# Chargers.net
KiCad netlist of a schematic drawn in Altium Designer
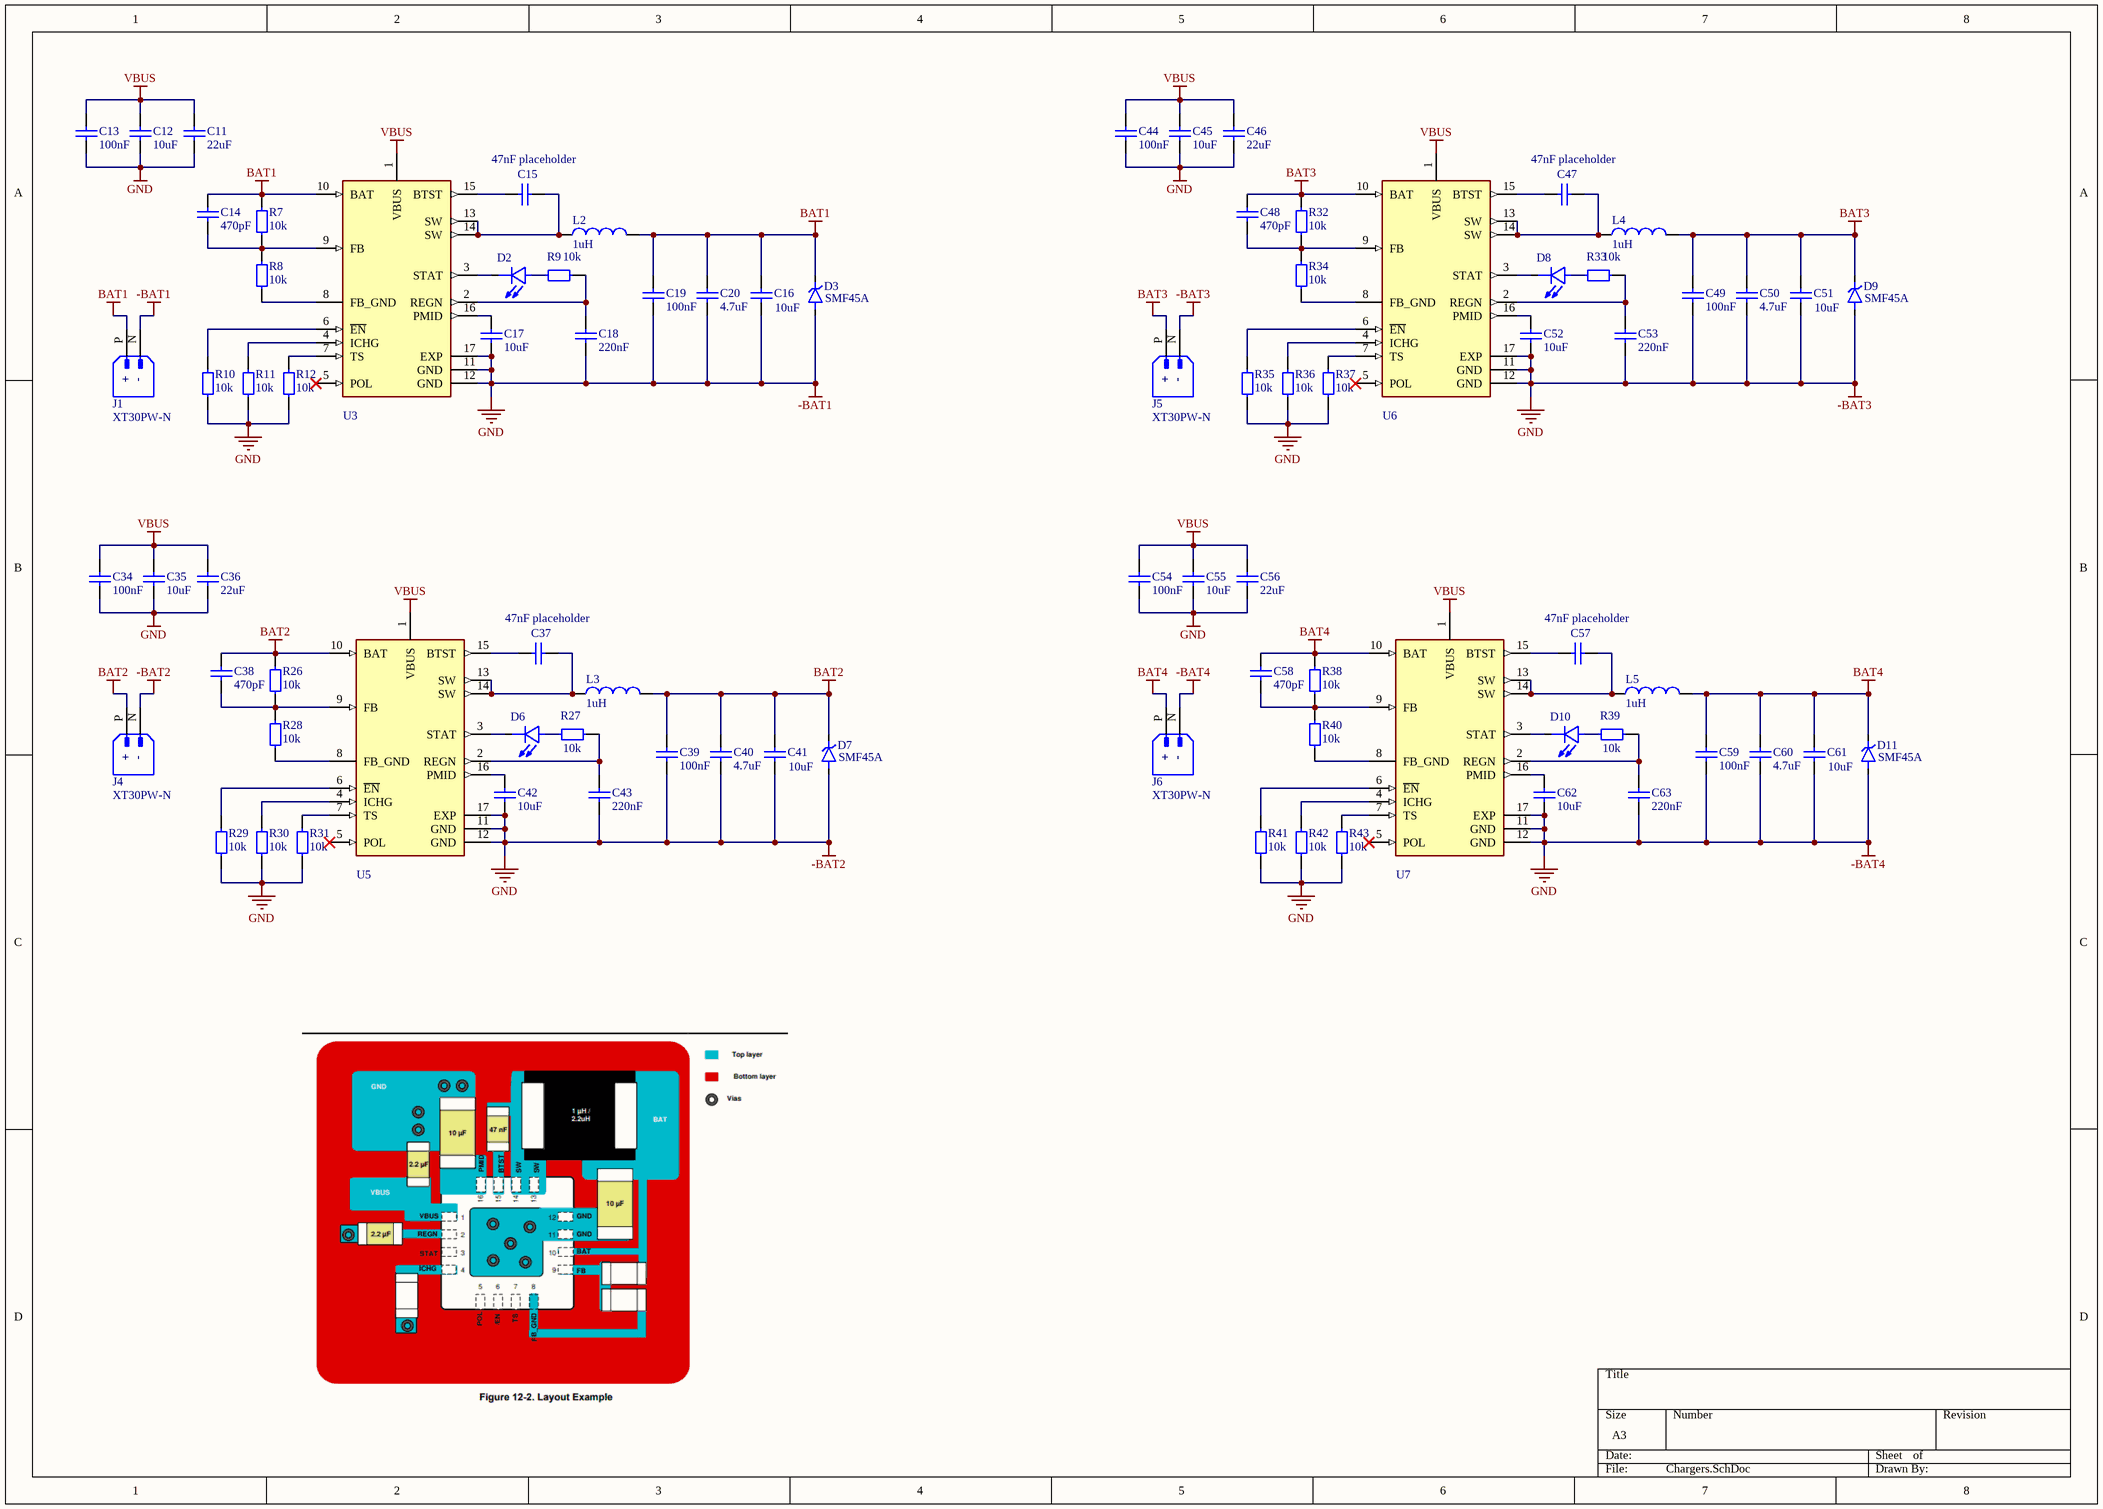
[diagram p0: Chargers.SchDoc]

(export (version "E")
  (design (tool "Eeschema 10.0.6"))
  (components
    (comp (ref "C11")
      (value "22uF")
      (footprint "1210_CAP")
      (description "22uF 50V 1210")
      (libsource (lib "Capacitor") (part "Capacitor 22uF 1210"))
    )
    (comp (ref "C12")
      (value "10uF")
      (footprint "0805_CAP")
      (description "10uF 50V 0805")
      (libsource (lib "Capacitor") (part "Capacitor 10uF 0805"))
    )
    (comp (ref "C13")
      (value "100nF")
      (footprint "0603 Capacitor")
      (description "100nF 50V 0603")
      (libsource (lib "Capacitor") (part "Capacitor 100nF 0603"))
    )
    (comp (ref "C14")
      (value "470pF")
      (footprint "0603 Capacitor")
      (description "470pF 50V 0603")
      (libsource (lib "Capacitor") (part "Capacitor 470pF 0603"))
    )
    (comp (ref "C15")
      (value "47nF placeholder")
      (footprint "0603 Capacitor")
      (description "1nF 50V 0603")
      (libsource (lib "Capacitor") (part "Capacitor 1nF 0603"))
    )
    (comp (ref "C16")
      (value "10uF")
      (footprint "0805_CAP")
      (description "10uF 50V 0805")
      (libsource (lib "Capacitor") (part "Capacitor 10uF 0805"))
    )
    (comp (ref "C17")
      (value "10uF")
      (footprint "0805_CAP")
      (description "10uF 50V 0805")
      (libsource (lib "Capacitor") (part "Capacitor 10uF 0805"))
    )
    (comp (ref "C18")
      (value "220nF")
      (footprint "0603 Capacitor")
      (description "220nF 50V 0603")
      (libsource (lib "Capacitor") (part "Capacitor 220nF 0603"))
    )
    (comp (ref "C19")
      (value "100nF")
      (footprint "0603 Capacitor")
      (description "100nF 50V 0603")
      (libsource (lib "Capacitor") (part "Capacitor 100nF 0603"))
    )
    (comp (ref "C20")
      (value "4.7uF")
      (footprint "0805_CAP")
      (description "4.7uF 50V 0805")
      (libsource (lib "Capacitor") (part "Capacitor 4.7uF 0805"))
    )
    (comp (ref "C34")
      (value "100nF")
      (footprint "0603 Capacitor")
      (description "100nF 50V 0603")
      (libsource (lib "Capacitor") (part "Capacitor 100nF 0603"))
    )
    (comp (ref "C35")
      (value "10uF")
      (footprint "0805_CAP")
      (description "10uF 50V 0805")
      (libsource (lib "Capacitor") (part "Capacitor 10uF 0805"))
    )
    (comp (ref "C36")
      (value "22uF")
      (footprint "1210_CAP")
      (description "22uF 50V 1210")
      (libsource (lib "Capacitor") (part "Capacitor 22uF 1210"))
    )
    (comp (ref "C37")
      (value "47nF placeholder")
      (footprint "0603 Capacitor")
      (description "1nF 50V 0603")
      (libsource (lib "Capacitor") (part "Capacitor 1nF 0603"))
    )
    (comp (ref "C38")
      (value "470pF")
      (footprint "0603 Capacitor")
      (description "470pF 50V 0603")
      (libsource (lib "Capacitor") (part "Capacitor 470pF 0603"))
    )
    (comp (ref "C39")
      (value "100nF")
      (footprint "0603 Capacitor")
      (description "100nF 50V 0603")
      (libsource (lib "Capacitor") (part "Capacitor 100nF 0603"))
    )
    (comp (ref "C40")
      (value "4.7uF")
      (footprint "0805_CAP")
      (description "4.7uF 50V 0805")
      (libsource (lib "Capacitor") (part "Capacitor 4.7uF 0805"))
    )
    (comp (ref "C41")
      (value "10uF")
      (footprint "0805_CAP")
      (description "10uF 50V 0805")
      (libsource (lib "Capacitor") (part "Capacitor 10uF 0805"))
    )
    (comp (ref "C42")
      (value "10uF")
      (footprint "0805_CAP")
      (description "10uF 50V 0805")
      (libsource (lib "Capacitor") (part "Capacitor 10uF 0805"))
    )
    (comp (ref "C43")
      (value "220nF")
      (footprint "0603 Capacitor")
      (description "220nF 50V 0603")
      (libsource (lib "Capacitor") (part "Capacitor 220nF 0603"))
    )
    (comp (ref "C44")
      (value "100nF")
      (footprint "0603 Capacitor")
      (description "100nF 50V 0603")
      (libsource (lib "Capacitor") (part "Capacitor 100nF 0603"))
    )
    (comp (ref "C45")
      (value "10uF")
      (footprint "0805_CAP")
      (description "10uF 50V 0805")
      (libsource (lib "Capacitor") (part "Capacitor 10uF 0805"))
    )
    (comp (ref "C46")
      (value "22uF")
      (footprint "1210_CAP")
      (description "22uF 50V 1210")
      (libsource (lib "Capacitor") (part "Capacitor 22uF 1210"))
    )
    (comp (ref "C47")
      (value "47nF placeholder")
      (footprint "0603 Capacitor")
      (description "1nF 50V 0603")
      (libsource (lib "Capacitor") (part "Capacitor 1nF 0603"))
    )
    (comp (ref "C48")
      (value "470pF")
      (footprint "0603 Capacitor")
      (description "470pF 50V 0603")
      (libsource (lib "Capacitor") (part "Capacitor 470pF 0603"))
    )
    (comp (ref "C49")
      (value "100nF")
      (footprint "0603 Capacitor")
      (description "100nF 50V 0603")
      (libsource (lib "Capacitor") (part "Capacitor 100nF 0603"))
    )
    (comp (ref "C50")
      (value "4.7uF")
      (footprint "0805_CAP")
      (description "4.7uF 50V 0805")
      (libsource (lib "Capacitor") (part "Capacitor 4.7uF 0805"))
    )
    (comp (ref "C51")
      (value "10uF")
      (footprint "0805_CAP")
      (description "10uF 50V 0805")
      (libsource (lib "Capacitor") (part "Capacitor 10uF 0805"))
    )
    (comp (ref "C52")
      (value "10uF")
      (footprint "0805_CAP")
      (description "10uF 50V 0805")
      (libsource (lib "Capacitor") (part "Capacitor 10uF 0805"))
    )
    (comp (ref "C53")
      (value "220nF")
      (footprint "0603 Capacitor")
      (description "220nF 50V 0603")
      (libsource (lib "Capacitor") (part "Capacitor 220nF 0603"))
    )
    (comp (ref "C54")
      (value "100nF")
      (footprint "0603 Capacitor")
      (description "100nF 50V 0603")
      (libsource (lib "Capacitor") (part "Capacitor 100nF 0603"))
    )
    (comp (ref "C55")
      (value "10uF")
      (footprint "0805_CAP")
      (description "10uF 50V 0805")
      (libsource (lib "Capacitor") (part "Capacitor 10uF 0805"))
    )
    (comp (ref "C56")
      (value "22uF")
      (footprint "1210_CAP")
      (description "22uF 50V 1210")
      (libsource (lib "Capacitor") (part "Capacitor 22uF 1210"))
    )
    (comp (ref "C57")
      (value "47nF placeholder")
      (footprint "0603 Capacitor")
      (description "1nF 50V 0603")
      (libsource (lib "Capacitor") (part "Capacitor 1nF 0603"))
    )
    (comp (ref "C58")
      (value "470pF")
      (footprint "0603 Capacitor")
      (description "470pF 50V 0603")
      (libsource (lib "Capacitor") (part "Capacitor 470pF 0603"))
    )
    (comp (ref "C59")
      (value "100nF")
      (footprint "0603 Capacitor")
      (description "100nF 50V 0603")
      (libsource (lib "Capacitor") (part "Capacitor 100nF 0603"))
    )
    (comp (ref "C60")
      (value "4.7uF")
      (footprint "0805_CAP")
      (description "4.7uF 50V 0805")
      (libsource (lib "Capacitor") (part "Capacitor 4.7uF 0805"))
    )
    (comp (ref "C61")
      (value "10uF")
      (footprint "0805_CAP")
      (description "10uF 50V 0805")
      (libsource (lib "Capacitor") (part "Capacitor 10uF 0805"))
    )
    (comp (ref "C62")
      (value "10uF")
      (footprint "0805_CAP")
      (description "10uF 50V 0805")
      (libsource (lib "Capacitor") (part "Capacitor 10uF 0805"))
    )
    (comp (ref "C63")
      (value "220nF")
      (footprint "0603 Capacitor")
      (description "220nF 50V 0603")
      (libsource (lib "Capacitor") (part "Capacitor 220nF 0603"))
    )
    (comp (ref "D2")
      (value "LTST-C190KGKT")
      (footprint "LED 0603")
      (description "1.6x0.8mm Smd Chip Led Lamp")
      (fields (field (name "MF") "Kingbright") (field (name "MP") "KPT-1608ZGC"))
      (libsource (lib "LED") (part "LED 0603"))
    )
    (comp (ref "D3")
      (value "SMF45A")
      (footprint "SOD3718X102N")
      (description "1-channel  50V ultra-low-capacitance IEC ESD protection diode")
      (fields (field (name "MF") "Texas Instruments") (field (name "MP") "TPD1E05U06DPYR"))
      (libsource (lib "TVS") (part "SMF45A"))
    )
    (comp (ref "D6")
      (value "LTST-C190KGKT")
      (footprint "LED 0603")
      (description "1.6x0.8mm Smd Chip Led Lamp")
      (fields (field (name "MF") "Kingbright") (field (name "MP") "KPT-1608ZGC"))
      (libsource (lib "LED") (part "LED 0603"))
    )
    (comp (ref "D7")
      (value "SMF45A")
      (footprint "SOD3718X102N")
      (description "1-channel  50V ultra-low-capacitance IEC ESD protection diode")
      (fields (field (name "MF") "Texas Instruments") (field (name "MP") "TPD1E05U06DPYR"))
      (libsource (lib "TVS") (part "SMF45A"))
    )
    (comp (ref "D8")
      (value "LTST-C190KGKT")
      (footprint "LED 0603")
      (description "1.6x0.8mm Smd Chip Led Lamp")
      (fields (field (name "MF") "Kingbright") (field (name "MP") "KPT-1608ZGC"))
      (libsource (lib "LED") (part "LED 0603"))
    )
    (comp (ref "D9")
      (value "SMF45A")
      (footprint "SOD3718X102N")
      (description "1-channel  50V ultra-low-capacitance IEC ESD protection diode")
      (fields (field (name "MF") "Texas Instruments") (field (name "MP") "TPD1E05U06DPYR"))
      (libsource (lib "TVS") (part "SMF45A"))
    )
    (comp (ref "D10")
      (value "LTST-C190KGKT")
      (footprint "LED 0603")
      (description "1.6x0.8mm Smd Chip Led Lamp")
      (fields (field (name "MF") "Kingbright") (field (name "MP") "KPT-1608ZGC"))
      (libsource (lib "LED") (part "LED 0603"))
    )
    (comp (ref "D11")
      (value "SMF45A")
      (footprint "SOD3718X102N")
      (description "1-channel  50V ultra-low-capacitance IEC ESD protection diode")
      (fields (field (name "MF") "Texas Instruments") (field (name "MP") "TPD1E05U06DPYR"))
      (libsource (lib "TVS") (part "SMF45A"))
    )
    (comp (ref "J1")
      (value "XT30PW-N")
      (footprint "AMASS_XT30UPB-M")
      (description "Socket; DC supply; XT30; male; PIN: 2; on PCBs; THT; straight, Colour: yellow")
      (fields (field (name "MF") "AMASS") (field (name "MP") "XT30PW-M"))
      (libsource (lib "Connector") (part "XT30PW-N"))
    )
    (comp (ref "J4")
      (value "XT30PW-N")
      (footprint "AMASS_XT30UPB-M")
      (description "Socket; DC supply; XT30; male; PIN: 2; on PCBs; THT; straight, Colour: yellow")
      (fields (field (name "MF") "AMASS") (field (name "MP") "XT30PW-M"))
      (libsource (lib "Connector") (part "XT30PW-N"))
    )
    (comp (ref "J5")
      (value "XT30PW-N")
      (footprint "AMASS_XT30UPB-M")
      (description "Socket; DC supply; XT30; male; PIN: 2; on PCBs; THT; straight, Colour: yellow")
      (fields (field (name "MF") "AMASS") (field (name "MP") "XT30PW-M"))
      (libsource (lib "Connector") (part "XT30PW-N"))
    )
    (comp (ref "J6")
      (value "XT30PW-N")
      (footprint "AMASS_XT30UPB-M")
      (description "Socket; DC supply; XT30; male; PIN: 2; on PCBs; THT; straight, Colour: yellow")
      (fields (field (name "MF") "AMASS") (field (name "MP") "XT30PW-M"))
      (libsource (lib "Connector") (part "XT30PW-N"))
    )
    (comp (ref "L2")
      (value "1uH")
      (footprint "HPPC05030")
      (description "1uH 9A  8.9mΩ")
      (fields (field (name "Comment") "HPPC05030-1R0M-Q8"))
      (libsource (lib "Inductor") (part "1uH 9A"))
    )
    (comp (ref "L3")
      (value "1uH")
      (footprint "HPPC05030")
      (description "1uH 9A  8.9mΩ")
      (fields (field (name "Comment") "HPPC05030-1R0M-Q8"))
      (libsource (lib "Inductor") (part "1uH 9A"))
    )
    (comp (ref "L4")
      (value "1uH")
      (footprint "HPPC05030")
      (description "1uH 9A  8.9mΩ")
      (fields (field (name "Comment") "HPPC05030-1R0M-Q8"))
      (libsource (lib "Inductor") (part "1uH 9A"))
    )
    (comp (ref "L5")
      (value "1uH")
      (footprint "HPPC05030")
      (description "1uH 9A  8.9mΩ")
      (fields (field (name "Comment") "HPPC05030-1R0M-Q8"))
      (libsource (lib "Inductor") (part "1uH 9A"))
    )
    (comp (ref "R7")
      (value "10k")
      (footprint "0603 Resistor")
      (description "10k 0603")
      (libsource (lib "Resistors") (part "Resistor 10k 0603"))
    )
    (comp (ref "R8")
      (value "10k")
      (footprint "0603 Resistor")
      (description "10k 0603")
      (libsource (lib "Resistors") (part "Resistor 10k 0603"))
    )
    (comp (ref "R9")
      (value "10k")
      (footprint "0603 Resistor")
      (description "10k 0603")
      (libsource (lib "Resistors") (part "Resistor 10k 0603"))
    )
    (comp (ref "R10")
      (value "10k")
      (footprint "0603 Resistor")
      (description "10k 0603")
      (libsource (lib "Resistors") (part "Resistor 10k 0603"))
    )
    (comp (ref "R11")
      (value "10k")
      (footprint "0603 Resistor")
      (description "10k 0603")
      (libsource (lib "Resistors") (part "Resistor 10k 0603"))
    )
    (comp (ref "R12")
      (value "10k")
      (footprint "0603 Resistor")
      (description "10k 0603")
      (libsource (lib "Resistors") (part "Resistor 10k 0603"))
    )
    (comp (ref "R26")
      (value "10k")
      (footprint "0603 Resistor")
      (description "10k 0603")
      (libsource (lib "Resistors") (part "Resistor 10k 0603"))
    )
    (comp (ref "R27")
      (value "10k")
      (footprint "0603 Resistor")
      (description "10k 0603")
      (libsource (lib "Resistors") (part "Resistor 10k 0603"))
    )
    (comp (ref "R28")
      (value "10k")
      (footprint "0603 Resistor")
      (description "10k 0603")
      (libsource (lib "Resistors") (part "Resistor 10k 0603"))
    )
    (comp (ref "R29")
      (value "10k")
      (footprint "0603 Resistor")
      (description "10k 0603")
      (libsource (lib "Resistors") (part "Resistor 10k 0603"))
    )
    (comp (ref "R30")
      (value "10k")
      (footprint "0603 Resistor")
      (description "10k 0603")
      (libsource (lib "Resistors") (part "Resistor 10k 0603"))
    )
    (comp (ref "R31")
      (value "10k")
      (footprint "0603 Resistor")
      (description "10k 0603")
      (libsource (lib "Resistors") (part "Resistor 10k 0603"))
    )
    (comp (ref "R32")
      (value "10k")
      (footprint "0603 Resistor")
      (description "10k 0603")
      (libsource (lib "Resistors") (part "Resistor 10k 0603"))
    )
    (comp (ref "R33")
      (value "10k")
      (footprint "0603 Resistor")
      (description "10k 0603")
      (libsource (lib "Resistors") (part "Resistor 10k 0603"))
    )
    (comp (ref "R34")
      (value "10k")
      (footprint "0603 Resistor")
      (description "10k 0603")
      (libsource (lib "Resistors") (part "Resistor 10k 0603"))
    )
    (comp (ref "R35")
      (value "10k")
      (footprint "0603 Resistor")
      (description "10k 0603")
      (libsource (lib "Resistors") (part "Resistor 10k 0603"))
    )
    (comp (ref "R36")
      (value "10k")
      (footprint "0603 Resistor")
      (description "10k 0603")
      (libsource (lib "Resistors") (part "Resistor 10k 0603"))
    )
    (comp (ref "R37")
      (value "10k")
      (footprint "0603 Resistor")
      (description "10k 0603")
      (libsource (lib "Resistors") (part "Resistor 10k 0603"))
    )
    (comp (ref "R38")
      (value "10k")
      (footprint "0603 Resistor")
      (description "10k 0603")
      (libsource (lib "Resistors") (part "Resistor 10k 0603"))
    )
    (comp (ref "R39")
      (value "10k")
      (footprint "0603 Resistor")
      (description "10k 0603")
      (libsource (lib "Resistors") (part "Resistor 10k 0603"))
    )
    (comp (ref "R40")
      (value "10k")
      (footprint "0603 Resistor")
      (description "10k 0603")
      (libsource (lib "Resistors") (part "Resistor 10k 0603"))
    )
    (comp (ref "R41")
      (value "10k")
      (footprint "0603 Resistor")
      (description "10k 0603")
      (libsource (lib "Resistors") (part "Resistor 10k 0603"))
    )
    (comp (ref "R42")
      (value "10k")
      (footprint "0603 Resistor")
      (description "10k 0603")
      (libsource (lib "Resistors") (part "Resistor 10k 0603"))
    )
    (comp (ref "R43")
      (value "10k")
      (footprint "0603 Resistor")
      (description "10k 0603")
      (libsource (lib "Resistors") (part "Resistor 10k 0603"))
    )
    (comp (ref "U3")
      (value "BQ25306RTER")
      (footprint "IC_BQ25306RTER")
      (description "TI Standalone 17-V, 3A 1-2 cell buck battery charger")
      (fields (field (name "MF") "Texas Instruments"))
      (libsource (lib "IC") (part "BQ25306RTER"))
    )
    (comp (ref "U5")
      (value "BQ25306RTER")
      (footprint "IC_BQ25306RTER")
      (description "TI Standalone 17-V, 3A 1-2 cell buck battery charger")
      (fields (field (name "MF") "Texas Instruments"))
      (libsource (lib "IC") (part "BQ25306RTER"))
    )
    (comp (ref "U6")
      (value "BQ25306RTER")
      (footprint "IC_BQ25306RTER")
      (description "TI Standalone 17-V, 3A 1-2 cell buck battery charger")
      (fields (field (name "MF") "Texas Instruments"))
      (libsource (lib "IC") (part "BQ25306RTER"))
    )
    (comp (ref "U7")
      (value "BQ25306RTER")
      (footprint "IC_BQ25306RTER")
      (description "TI Standalone 17-V, 3A 1-2 cell buck battery charger")
      (fields (field (name "MF") "Texas Instruments"))
      (libsource (lib "IC") (part "BQ25306RTER"))
    )
  )
  (nets
    (net (code "1") (name "-BAT1") (class "Default")
      (node (ref "C11") (pin "2") (pinfunction "2_2") (pintype "passive"))
      (node (ref "C12") (pin "2") (pinfunction "2_2") (pintype "passive"))
      (node (ref "C13") (pin "2") (pinfunction "2_2") (pintype "passive"))
      (node (ref "C16") (pin "1") (pinfunction "1_1") (pintype "passive"))
      (node (ref "C17") (pin "1") (pinfunction "1_1") (pintype "passive"))
      (node (ref "C18") (pin "1") (pinfunction "1_1") (pintype "passive"))
      (node (ref "C19") (pin "1") (pinfunction "1_1") (pintype "passive"))
      (node (ref "C20") (pin "1") (pinfunction "1_1") (pintype "passive"))
      (node (ref "C34") (pin "2") (pinfunction "2_2") (pintype "passive"))
      (node (ref "C35") (pin "2") (pinfunction "2_2") (pintype "passive"))
      (node (ref "C36") (pin "2") (pinfunction "2_2") (pintype "passive"))
      (node (ref "C39") (pin "1") (pinfunction "1_1") (pintype "passive"))
      (node (ref "C40") (pin "1") (pinfunction "1_1") (pintype "passive"))
      (node (ref "C41") (pin "1") (pinfunction "1_1") (pintype "passive"))
      (node (ref "C42") (pin "1") (pinfunction "1_1") (pintype "passive"))
      (node (ref "C43") (pin "1") (pinfunction "1_1") (pintype "passive"))
      (node (ref "C44") (pin "2") (pinfunction "2_2") (pintype "passive"))
      (node (ref "C45") (pin "2") (pinfunction "2_2") (pintype "passive"))
      (node (ref "C46") (pin "2") (pinfunction "2_2") (pintype "passive"))
      (node (ref "C49") (pin "1") (pinfunction "1_1") (pintype "passive"))
      (node (ref "C50") (pin "1") (pinfunction "1_1") (pintype "passive"))
      (node (ref "C51") (pin "1") (pinfunction "1_1") (pintype "passive"))
      (node (ref "C52") (pin "1") (pinfunction "1_1") (pintype "passive"))
      (node (ref "C53") (pin "1") (pinfunction "1_1") (pintype "passive"))
      (node (ref "C54") (pin "2") (pinfunction "2_2") (pintype "passive"))
      (node (ref "C55") (pin "2") (pinfunction "2_2") (pintype "passive"))
      (node (ref "C56") (pin "2") (pinfunction "2_2") (pintype "passive"))
      (node (ref "C59") (pin "1") (pinfunction "1_1") (pintype "passive"))
      (node (ref "C60") (pin "1") (pinfunction "1_1") (pintype "passive"))
      (node (ref "C61") (pin "1") (pinfunction "1_1") (pintype "passive"))
      (node (ref "C62") (pin "1") (pinfunction "1_1") (pintype "passive"))
      (node (ref "C63") (pin "1") (pinfunction "1_1") (pintype "passive"))
      (node (ref "D11") (pin "A") (pinfunction "2_A") (pintype "passive"))
      (node (ref "D3") (pin "A") (pinfunction "2_A") (pintype "passive"))
      (node (ref "D7") (pin "A") (pinfunction "2_A") (pintype "passive"))
      (node (ref "D9") (pin "A") (pinfunction "2_A") (pintype "passive"))
      (node (ref "J1") (pin "N") (pinfunction "N_N") (pintype "power_in"))
      (node (ref "J4") (pin "N") (pinfunction "N_N") (pintype "power_in"))
      (node (ref "J5") (pin "N") (pinfunction "N_N") (pintype "power_in"))
      (node (ref "J6") (pin "N") (pinfunction "N_N") (pintype "power_in"))
      (node (ref "R10") (pin "1") (pinfunction "CCW_1") (pintype "passive"))
      (node (ref "R11") (pin "1") (pinfunction "CCW_1") (pintype "passive"))
      (node (ref "R12") (pin "1") (pinfunction "CCW_1") (pintype "passive"))
      (node (ref "R29") (pin "1") (pinfunction "CCW_1") (pintype "passive"))
      (node (ref "R30") (pin "1") (pinfunction "CCW_1") (pintype "passive"))
      (node (ref "R31") (pin "1") (pinfunction "CCW_1") (pintype "passive"))
      (node (ref "R35") (pin "1") (pinfunction "CCW_1") (pintype "passive"))
      (node (ref "R36") (pin "1") (pinfunction "CCW_1") (pintype "passive"))
      (node (ref "R37") (pin "1") (pinfunction "CCW_1") (pintype "passive"))
      (node (ref "R41") (pin "1") (pinfunction "CCW_1") (pintype "passive"))
      (node (ref "R42") (pin "1") (pinfunction "CCW_1") (pintype "passive"))
      (node (ref "R43") (pin "1") (pinfunction "CCW_1") (pintype "passive"))
      (node (ref "U3") (pin "11") (pinfunction "GND_11") (pintype "power_in"))
      (node (ref "U3") (pin "12") (pinfunction "GND_12") (pintype "power_in"))
      (node (ref "U3") (pin "17") (pinfunction "EXP_17") (pintype "power_in"))
      (node (ref "U5") (pin "11") (pinfunction "GND_11") (pintype "power_in"))
      (node (ref "U5") (pin "12") (pinfunction "GND_12") (pintype "power_in"))
      (node (ref "U5") (pin "17") (pinfunction "EXP_17") (pintype "power_in"))
      (node (ref "U6") (pin "11") (pinfunction "GND_11") (pintype "power_in"))
      (node (ref "U6") (pin "12") (pinfunction "GND_12") (pintype "power_in"))
      (node (ref "U6") (pin "17") (pinfunction "EXP_17") (pintype "power_in"))
      (node (ref "U7") (pin "11") (pinfunction "GND_11") (pintype "power_in"))
      (node (ref "U7") (pin "12") (pinfunction "GND_12") (pintype "power_in"))
      (node (ref "U7") (pin "17") (pinfunction "EXP_17") (pintype "power_in"))
    )
    (net (code "2") (name "BAT1") (class "Default")
      (node (ref "C14") (pin "2") (pinfunction "2_2") (pintype "passive"))
      (node (ref "C16") (pin "2") (pinfunction "2_2") (pintype "passive"))
      (node (ref "C19") (pin "2") (pinfunction "2_2") (pintype "passive"))
      (node (ref "C20") (pin "2") (pinfunction "2_2") (pintype "passive"))
      (node (ref "D3") (pin "C") (pinfunction "K1_C") (pintype "passive"))
      (node (ref "J1") (pin "P") (pinfunction "+_P") (pintype "power_in"))
      (node (ref "L2") (pin "2") (pinfunction "2_2") (pintype "passive"))
      (node (ref "R7") (pin "2") (pinfunction "CW_2") (pintype "passive"))
      (node (ref "U3") (pin "10") (pinfunction "BAT_10") (pintype "input"))
    )
    (net (code "3") (name "BAT2") (class "Default")
      (node (ref "C38") (pin "2") (pinfunction "2_2") (pintype "passive"))
      (node (ref "C39") (pin "2") (pinfunction "2_2") (pintype "passive"))
      (node (ref "C40") (pin "2") (pinfunction "2_2") (pintype "passive"))
      (node (ref "C41") (pin "2") (pinfunction "2_2") (pintype "passive"))
      (node (ref "D7") (pin "C") (pinfunction "K1_C") (pintype "passive"))
      (node (ref "J4") (pin "P") (pinfunction "+_P") (pintype "power_in"))
      (node (ref "L3") (pin "2") (pinfunction "2_2") (pintype "passive"))
      (node (ref "R26") (pin "2") (pinfunction "CW_2") (pintype "passive"))
      (node (ref "U5") (pin "10") (pinfunction "BAT_10") (pintype "input"))
    )
    (net (code "4") (name "BAT3") (class "Default")
      (node (ref "C48") (pin "2") (pinfunction "2_2") (pintype "passive"))
      (node (ref "C49") (pin "2") (pinfunction "2_2") (pintype "passive"))
      (node (ref "C50") (pin "2") (pinfunction "2_2") (pintype "passive"))
      (node (ref "C51") (pin "2") (pinfunction "2_2") (pintype "passive"))
      (node (ref "D9") (pin "C") (pinfunction "K1_C") (pintype "passive"))
      (node (ref "J5") (pin "P") (pinfunction "+_P") (pintype "power_in"))
      (node (ref "L4") (pin "2") (pinfunction "2_2") (pintype "passive"))
      (node (ref "R32") (pin "2") (pinfunction "CW_2") (pintype "passive"))
      (node (ref "U6") (pin "10") (pinfunction "BAT_10") (pintype "input"))
    )
    (net (code "5") (name "BAT4") (class "Default")
      (node (ref "C58") (pin "2") (pinfunction "2_2") (pintype "passive"))
      (node (ref "C59") (pin "2") (pinfunction "2_2") (pintype "passive"))
      (node (ref "C60") (pin "2") (pinfunction "2_2") (pintype "passive"))
      (node (ref "C61") (pin "2") (pinfunction "2_2") (pintype "passive"))
      (node (ref "D11") (pin "C") (pinfunction "K1_C") (pintype "passive"))
      (node (ref "J6") (pin "P") (pinfunction "+_P") (pintype "power_in"))
      (node (ref "L5") (pin "2") (pinfunction "2_2") (pintype "passive"))
      (node (ref "R38") (pin "2") (pinfunction "CW_2") (pintype "passive"))
      (node (ref "U7") (pin "10") (pinfunction "BAT_10") (pintype "input"))
    )
    (net (code "6") (name "Net-(C15-Pad1)") (class "Default")
      (node (ref "C15") (pin "1") (pinfunction "1_1") (pintype "passive"))
      (node (ref "L2") (pin "1") (pinfunction "1_1") (pintype "passive"))
      (node (ref "U3") (pin "13") (pinfunction "SW_13") (pintype "output"))
      (node (ref "U3") (pin "14") (pinfunction "SW_14") (pintype "output"))
    )
    (net (code "7") (name "Net-(C37-Pad1)") (class "Default")
      (node (ref "C37") (pin "1") (pinfunction "1_1") (pintype "passive"))
      (node (ref "L3") (pin "1") (pinfunction "1_1") (pintype "passive"))
      (node (ref "U5") (pin "13") (pinfunction "SW_13") (pintype "output"))
      (node (ref "U5") (pin "14") (pinfunction "SW_14") (pintype "output"))
    )
    (net (code "8") (name "Net-(C47-Pad1)") (class "Default")
      (node (ref "C47") (pin "1") (pinfunction "1_1") (pintype "passive"))
      (node (ref "L4") (pin "1") (pinfunction "1_1") (pintype "passive"))
      (node (ref "U6") (pin "13") (pinfunction "SW_13") (pintype "output"))
      (node (ref "U6") (pin "14") (pinfunction "SW_14") (pintype "output"))
    )
    (net (code "9") (name "Net-(C57-Pad1)") (class "Default")
      (node (ref "C57") (pin "1") (pinfunction "1_1") (pintype "passive"))
      (node (ref "L5") (pin "1") (pinfunction "1_1") (pintype "passive"))
      (node (ref "U7") (pin "13") (pinfunction "SW_13") (pintype "output"))
      (node (ref "U7") (pin "14") (pinfunction "SW_14") (pintype "output"))
    )
    (net (code "10") (name "Net-(D2-A)") (class "Default")
      (node (ref "D2") (pin "1") (pinfunction "A_1") (pintype "passive"))
      (node (ref "R9") (pin "2") (pinfunction "CW_2") (pintype "passive"))
    )
    (net (code "11") (name "Net-(D2-C)") (class "Default")
      (node (ref "D2") (pin "2") (pinfunction "C_2") (pintype "passive"))
      (node (ref "U3") (pin "3") (pinfunction "STAT_3") (pintype "output"))
    )
    (net (code "12") (name "Net-(D6-A)") (class "Default")
      (node (ref "D6") (pin "1") (pinfunction "A_1") (pintype "passive"))
      (node (ref "R27") (pin "2") (pinfunction "CW_2") (pintype "passive"))
    )
    (net (code "13") (name "Net-(D6-C)") (class "Default")
      (node (ref "D6") (pin "2") (pinfunction "C_2") (pintype "passive"))
      (node (ref "U5") (pin "3") (pinfunction "STAT_3") (pintype "output"))
    )
    (net (code "14") (name "Net-(D8-A)") (class "Default")
      (node (ref "D8") (pin "1") (pinfunction "A_1") (pintype "passive"))
      (node (ref "R33") (pin "2") (pinfunction "CW_2") (pintype "passive"))
    )
    (net (code "15") (name "Net-(D8-C)") (class "Default")
      (node (ref "D8") (pin "2") (pinfunction "C_2") (pintype "passive"))
      (node (ref "U6") (pin "3") (pinfunction "STAT_3") (pintype "output"))
    )
    (net (code "16") (name "Net-(D10-A)") (class "Default")
      (node (ref "D10") (pin "1") (pinfunction "A_1") (pintype "passive"))
      (node (ref "R39") (pin "2") (pinfunction "CW_2") (pintype "passive"))
    )
    (net (code "17") (name "Net-(D10-C)") (class "Default")
      (node (ref "D10") (pin "2") (pinfunction "C_2") (pintype "passive"))
      (node (ref "U7") (pin "3") (pinfunction "STAT_3") (pintype "output"))
    )
    (net (code "18") (name "Net-(R7-CCW)") (class "Default")
      (node (ref "C14") (pin "1") (pinfunction "1_1") (pintype "passive"))
      (node (ref "R7") (pin "1") (pinfunction "CCW_1") (pintype "passive"))
      (node (ref "R8") (pin "2") (pinfunction "CW_2") (pintype "passive"))
      (node (ref "U3") (pin "9") (pinfunction "FB_9") (pintype "input"))
    )
    (net (code "19") (name "Net-(R8-CCW)") (class "Default")
      (node (ref "R8") (pin "1") (pinfunction "CCW_1") (pintype "passive"))
      (node (ref "U3") (pin "8") (pinfunction "FB_GND_8") (pintype "power_in"))
    )
    (net (code "20") (name "Net-(R9-CCW)") (class "Default")
      (node (ref "C18") (pin "2") (pinfunction "2_2") (pintype "passive"))
      (node (ref "R9") (pin "1") (pinfunction "CCW_1") (pintype "passive"))
      (node (ref "U3") (pin "2") (pinfunction "REGN_2") (pintype "output"))
    )
    (net (code "21") (name "Net-(R10-CW)") (class "Default")
      (node (ref "R10") (pin "2") (pinfunction "CW_2") (pintype "passive"))
      (node (ref "U3") (pin "6") (pinfunction "~{EN}_6") (pintype "input"))
    )
    (net (code "22") (name "Net-(R11-CW)") (class "Default")
      (node (ref "R11") (pin "2") (pinfunction "CW_2") (pintype "passive"))
      (node (ref "U3") (pin "4") (pinfunction "ICHG_4") (pintype "input"))
    )
    (net (code "23") (name "Net-(R12-CW)") (class "Default")
      (node (ref "R12") (pin "2") (pinfunction "CW_2") (pintype "passive"))
      (node (ref "U3") (pin "7") (pinfunction "TS_7") (pintype "input"))
    )
    (net (code "24") (name "Net-(R26-CCW)") (class "Default")
      (node (ref "C38") (pin "1") (pinfunction "1_1") (pintype "passive"))
      (node (ref "R26") (pin "1") (pinfunction "CCW_1") (pintype "passive"))
      (node (ref "R28") (pin "2") (pinfunction "CW_2") (pintype "passive"))
      (node (ref "U5") (pin "9") (pinfunction "FB_9") (pintype "input"))
    )
    (net (code "25") (name "Net-(R27-CCW)") (class "Default")
      (node (ref "C43") (pin "2") (pinfunction "2_2") (pintype "passive"))
      (node (ref "R27") (pin "1") (pinfunction "CCW_1") (pintype "passive"))
      (node (ref "U5") (pin "2") (pinfunction "REGN_2") (pintype "output"))
    )
    (net (code "26") (name "Net-(R28-CCW)") (class "Default")
      (node (ref "R28") (pin "1") (pinfunction "CCW_1") (pintype "passive"))
      (node (ref "U5") (pin "8") (pinfunction "FB_GND_8") (pintype "power_in"))
    )
    (net (code "27") (name "Net-(R29-CW)") (class "Default")
      (node (ref "R29") (pin "2") (pinfunction "CW_2") (pintype "passive"))
      (node (ref "U5") (pin "6") (pinfunction "~{EN}_6") (pintype "input"))
    )
    (net (code "28") (name "Net-(R30-CW)") (class "Default")
      (node (ref "R30") (pin "2") (pinfunction "CW_2") (pintype "passive"))
      (node (ref "U5") (pin "4") (pinfunction "ICHG_4") (pintype "input"))
    )
    (net (code "29") (name "Net-(R31-CW)") (class "Default")
      (node (ref "R31") (pin "2") (pinfunction "CW_2") (pintype "passive"))
      (node (ref "U5") (pin "7") (pinfunction "TS_7") (pintype "input"))
    )
    (net (code "30") (name "Net-(R32-CCW)") (class "Default")
      (node (ref "C48") (pin "1") (pinfunction "1_1") (pintype "passive"))
      (node (ref "R32") (pin "1") (pinfunction "CCW_1") (pintype "passive"))
      (node (ref "R34") (pin "2") (pinfunction "CW_2") (pintype "passive"))
      (node (ref "U6") (pin "9") (pinfunction "FB_9") (pintype "input"))
    )
    (net (code "31") (name "Net-(R33-CCW)") (class "Default")
      (node (ref "C53") (pin "2") (pinfunction "2_2") (pintype "passive"))
      (node (ref "R33") (pin "1") (pinfunction "CCW_1") (pintype "passive"))
      (node (ref "U6") (pin "2") (pinfunction "REGN_2") (pintype "output"))
    )
    (net (code "32") (name "Net-(R34-CCW)") (class "Default")
      (node (ref "R34") (pin "1") (pinfunction "CCW_1") (pintype "passive"))
      (node (ref "U6") (pin "8") (pinfunction "FB_GND_8") (pintype "power_in"))
    )
    (net (code "33") (name "Net-(R35-CW)") (class "Default")
      (node (ref "R35") (pin "2") (pinfunction "CW_2") (pintype "passive"))
      (node (ref "U6") (pin "6") (pinfunction "~{EN}_6") (pintype "input"))
    )
    (net (code "34") (name "Net-(R36-CW)") (class "Default")
      (node (ref "R36") (pin "2") (pinfunction "CW_2") (pintype "passive"))
      (node (ref "U6") (pin "4") (pinfunction "ICHG_4") (pintype "input"))
    )
    (net (code "35") (name "Net-(R37-CW)") (class "Default")
      (node (ref "R37") (pin "2") (pinfunction "CW_2") (pintype "passive"))
      (node (ref "U6") (pin "7") (pinfunction "TS_7") (pintype "input"))
    )
    (net (code "36") (name "Net-(R38-CCW)") (class "Default")
      (node (ref "C58") (pin "1") (pinfunction "1_1") (pintype "passive"))
      (node (ref "R38") (pin "1") (pinfunction "CCW_1") (pintype "passive"))
      (node (ref "R40") (pin "2") (pinfunction "CW_2") (pintype "passive"))
      (node (ref "U7") (pin "9") (pinfunction "FB_9") (pintype "input"))
    )
    (net (code "37") (name "Net-(R39-CCW)") (class "Default")
      (node (ref "C63") (pin "2") (pinfunction "2_2") (pintype "passive"))
      (node (ref "R39") (pin "1") (pinfunction "CCW_1") (pintype "passive"))
      (node (ref "U7") (pin "2") (pinfunction "REGN_2") (pintype "output"))
    )
    (net (code "38") (name "Net-(R40-CCW)") (class "Default")
      (node (ref "R40") (pin "1") (pinfunction "CCW_1") (pintype "passive"))
      (node (ref "U7") (pin "8") (pinfunction "FB_GND_8") (pintype "power_in"))
    )
    (net (code "39") (name "Net-(R41-CW)") (class "Default")
      (node (ref "R41") (pin "2") (pinfunction "CW_2") (pintype "passive"))
      (node (ref "U7") (pin "6") (pinfunction "~{EN}_6") (pintype "input"))
    )
    (net (code "40") (name "Net-(R42-CW)") (class "Default")
      (node (ref "R42") (pin "2") (pinfunction "CW_2") (pintype "passive"))
      (node (ref "U7") (pin "4") (pinfunction "ICHG_4") (pintype "input"))
    )
    (net (code "41") (name "Net-(R43-CW)") (class "Default")
      (node (ref "R43") (pin "2") (pinfunction "CW_2") (pintype "passive"))
      (node (ref "U7") (pin "7") (pinfunction "TS_7") (pintype "input"))
    )
    (net (code "42") (name "Net-(U3-BTST)") (class "Default")
      (node (ref "C15") (pin "2") (pinfunction "2_2") (pintype "passive"))
      (node (ref "U3") (pin "15") (pinfunction "BTST_15") (pintype "output"))
    )
    (net (code "43") (name "Net-(U3-PMID)") (class "Default")
      (node (ref "C17") (pin "2") (pinfunction "2_2") (pintype "passive"))
      (node (ref "U3") (pin "16") (pinfunction "PMID_16") (pintype "output"))
    )
    (net (code "44") (name "Net-(U5-BTST)") (class "Default")
      (node (ref "C37") (pin "2") (pinfunction "2_2") (pintype "passive"))
      (node (ref "U5") (pin "15") (pinfunction "BTST_15") (pintype "output"))
    )
    (net (code "45") (name "Net-(U5-PMID)") (class "Default")
      (node (ref "C42") (pin "2") (pinfunction "2_2") (pintype "passive"))
      (node (ref "U5") (pin "16") (pinfunction "PMID_16") (pintype "output"))
    )
    (net (code "46") (name "Net-(U6-BTST)") (class "Default")
      (node (ref "C47") (pin "2") (pinfunction "2_2") (pintype "passive"))
      (node (ref "U6") (pin "15") (pinfunction "BTST_15") (pintype "output"))
    )
    (net (code "47") (name "Net-(U6-PMID)") (class "Default")
      (node (ref "C52") (pin "2") (pinfunction "2_2") (pintype "passive"))
      (node (ref "U6") (pin "16") (pinfunction "PMID_16") (pintype "output"))
    )
    (net (code "48") (name "Net-(U7-BTST)") (class "Default")
      (node (ref "C57") (pin "2") (pinfunction "2_2") (pintype "passive"))
      (node (ref "U7") (pin "15") (pinfunction "BTST_15") (pintype "output"))
    )
    (net (code "49") (name "Net-(U7-PMID)") (class "Default")
      (node (ref "C62") (pin "2") (pinfunction "2_2") (pintype "passive"))
      (node (ref "U7") (pin "16") (pinfunction "PMID_16") (pintype "output"))
    )
    (net (code "50") (name "VBUS") (class "Default")
      (node (ref "C11") (pin "1") (pinfunction "1_1") (pintype "passive"))
      (node (ref "C12") (pin "1") (pinfunction "1_1") (pintype "passive"))
      (node (ref "C13") (pin "1") (pinfunction "1_1") (pintype "passive"))
      (node (ref "C34") (pin "1") (pinfunction "1_1") (pintype "passive"))
      (node (ref "C35") (pin "1") (pinfunction "1_1") (pintype "passive"))
      (node (ref "C36") (pin "1") (pinfunction "1_1") (pintype "passive"))
      (node (ref "C44") (pin "1") (pinfunction "1_1") (pintype "passive"))
      (node (ref "C45") (pin "1") (pinfunction "1_1") (pintype "passive"))
      (node (ref "C46") (pin "1") (pinfunction "1_1") (pintype "passive"))
      (node (ref "C54") (pin "1") (pinfunction "1_1") (pintype "passive"))
      (node (ref "C55") (pin "1") (pinfunction "1_1") (pintype "passive"))
      (node (ref "C56") (pin "1") (pinfunction "1_1") (pintype "passive"))
      (node (ref "U3") (pin "1") (pinfunction "VBUS_1") (pintype "power_in"))
      (node (ref "U5") (pin "1") (pinfunction "VBUS_1") (pintype "power_in"))
      (node (ref "U6") (pin "1") (pinfunction "VBUS_1") (pintype "power_in"))
      (node (ref "U7") (pin "1") (pinfunction "VBUS_1") (pintype "power_in"))
    )
    (net (code "51") (name "unconnected-(U3-POL-Pad5)") (class "Default")
      (node (ref "U3") (pin "5") (pinfunction "POL_5") (pintype "input+no_connect"))
    )
    (net (code "52") (name "unconnected-(U5-POL-Pad5)") (class "Default")
      (node (ref "U5") (pin "5") (pinfunction "POL_5") (pintype "input+no_connect"))
    )
    (net (code "53") (name "unconnected-(U6-POL-Pad5)") (class "Default")
      (node (ref "U6") (pin "5") (pinfunction "POL_5") (pintype "input+no_connect"))
    )
    (net (code "54") (name "unconnected-(U7-POL-Pad5)") (class "Default")
      (node (ref "U7") (pin "5") (pinfunction "POL_5") (pintype "input+no_connect"))
    )
  )
)
